# esp_breakout.net
KiCad netlist of a schematic drawn in EAGLE
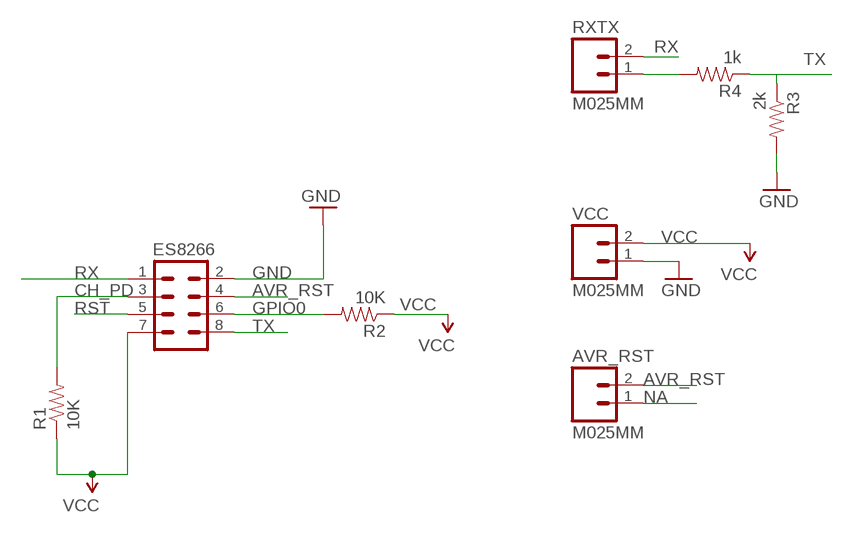
[diagram p0: schematic, sheet 1]

(export (version "E")
  (design (tool "Eeschema 10.0.6"))
  (components
    (comp (ref "AVR_RST")
      (value "M025MM")
      (footprint "eagle-import:SCREWTERMINAL-5MM-2")
      (libsource (lib "eagle-import") (part "M025MM"))
    )
    (comp (ref "ES8266")
      (value "M04X2")
      (footprint "eagle-import:2X4")
      (libsource (lib "eagle-import") (part "M04X2"))
    )
    (comp (ref "R1")
      (value "10K")
      (footprint "eagle-import:AXIAL-0.3")
      (libsource (lib "eagle-import") (part "1KOHM-1/4W-1%(PTH)"))
    )
    (comp (ref "R2")
      (value "10K")
      (footprint "eagle-import:AXIAL-0.3")
      (libsource (lib "eagle-import") (part "1KOHM-1/4W-1%(PTH)"))
    )
    (comp (ref "R3")
      (value "2k")
      (footprint "eagle-import:AXIAL-0.3")
      (libsource (lib "eagle-import") (part "1KOHM-1/4W-1%(PTH)"))
    )
    (comp (ref "R4")
      (value "1k")
      (footprint "eagle-import:AXIAL-0.3")
      (libsource (lib "eagle-import") (part "1KOHM-1/4W-1%(PTH)"))
    )
    (comp (ref "RXTX")
      (value "M025MM")
      (footprint "eagle-import:SCREWTERMINAL-5MM-2")
      (libsource (lib "eagle-import") (part "M025MM"))
    )
    (comp (ref "VCC")
      (value "M025MM")
      (footprint "eagle-import:SCREWTERMINAL-5MM-2")
      (libsource (lib "eagle-import") (part "M025MM"))
    )
  )
  (nets
    (net (code "1") (name "/AVR_RST") (class "Default")
      (node (ref "AVR_RST") (pin "2") (pinfunction "2_2") (pintype "passive"))
      (node (ref "ES8266") (pin "4") (pinfunction "4_4") (pintype "passive"))
    )
    (net (code "2") (name "/CH_PD") (class "Default")
      (node (ref "ES8266") (pin "3") (pinfunction "3_3") (pintype "passive"))
      (node (ref "R1") (pin "P$2") (pinfunction "2_P$2") (pintype "passive"))
    )
    (net (code "3") (name "/GPIO0") (class "Default")
      (node (ref "ES8266") (pin "6") (pinfunction "6_6") (pintype "passive"))
      (node (ref "R2") (pin "P$2") (pinfunction "2_P$2") (pintype "passive"))
    )
    (net (code "4") (name "/NA") (class "Default")
      (node (ref "AVR_RST") (pin "1") (pinfunction "1_1") (pintype "passive"))
    )
    (net (code "5") (name "/RST") (class "Default")
      (node (ref "ES8266") (pin "5") (pinfunction "5_5") (pintype "passive"))
    )
    (net (code "6") (name "/RX") (class "Default")
      (node (ref "ES8266") (pin "1") (pinfunction "1_1") (pintype "passive"))
      (node (ref "RXTX") (pin "2") (pinfunction "2_2") (pintype "passive"))
    )
    (net (code "7") (name "/TX") (class "Default")
      (node (ref "ES8266") (pin "8") (pinfunction "8_8") (pintype "passive"))
      (node (ref "R3") (pin "P$1") (pinfunction "1_P$1") (pintype "passive"))
      (node (ref "R4") (pin "P$1") (pinfunction "1_P$1") (pintype "passive"))
    )
    (net (code "8") (name "GND") (class "Default")
      (node (ref "ES8266") (pin "2") (pinfunction "2_2") (pintype "passive"))
      (node (ref "R3") (pin "P$2") (pinfunction "2_P$2") (pintype "passive"))
      (node (ref "VCC") (pin "1") (pinfunction "1_1") (pintype "passive"))
    )
    (net (code "9") (name "Net-(R4-2)") (class "Default")
      (node (ref "R4") (pin "P$2") (pinfunction "2_P$2") (pintype "passive"))
      (node (ref "RXTX") (pin "1") (pinfunction "1_1") (pintype "passive"))
    )
    (net (code "10") (name "VCC") (class "Default")
      (node (ref "ES8266") (pin "7") (pinfunction "7_7") (pintype "passive"))
      (node (ref "R1") (pin "P$1") (pinfunction "1_P$1") (pintype "passive"))
      (node (ref "R2") (pin "P$1") (pinfunction "1_P$1") (pintype "passive"))
      (node (ref "VCC") (pin "2") (pinfunction "2_2") (pintype "passive"))
    )
  )
)
